# USB.net
KiCad netlist of a schematic drawn in Altium Designer
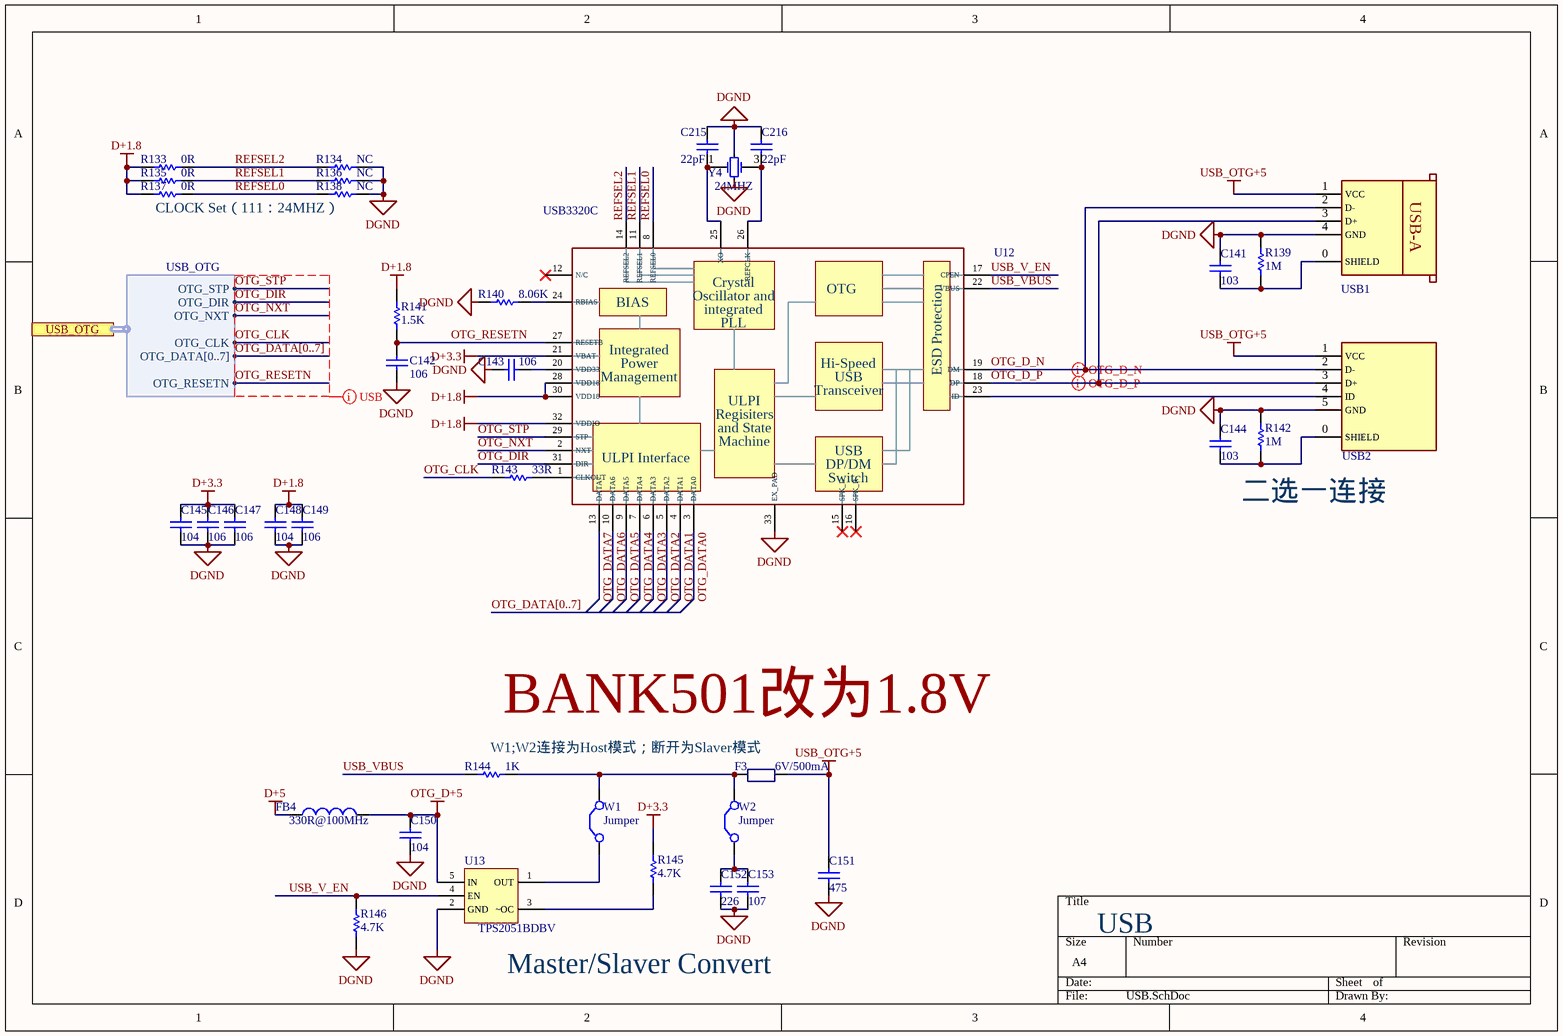
[diagram p0: USB.SchDoc]

(export (version "E")
  (design (tool "Eeschema 10.0.6"))
  (components
    (comp (ref "C141")
      (value "103")
      (footprint "C 0603_L")
      (description "Capacitor")
      (fields (field (name "PUBLISHER") "Altium Limited"))
      (libsource (lib "Miscellaneous Devices") (part "Cap"))
    )
    (comp (ref "C142")
      (value "106")
      (footprint "C 0603_L")
      (description "Capacitor")
      (fields (field (name "PUBLISHER") "Altium Limited"))
      (libsource (lib "Miscellaneous Devices") (part "Cap"))
    )
    (comp (ref "C143")
      (value "106")
      (footprint "C 0603_L")
      (description "Capacitor")
      (fields (field (name "PUBLISHER") "Altium Limited"))
      (libsource (lib "Miscellaneous Devices") (part "Cap"))
    )
    (comp (ref "C144")
      (value "103")
      (footprint "C 0603_L")
      (description "Capacitor")
      (fields (field (name "PUBLISHER") "Altium Limited"))
      (libsource (lib "Miscellaneous Devices") (part "Cap"))
    )
    (comp (ref "C145")
      (value "104")
      (footprint "C 0402_LL")
      (description "Capacitor")
      (fields (field (name "PUBLISHER") "Altium Limited"))
      (libsource (lib "Miscellaneous Devices") (part "Cap"))
    )
    (comp (ref "C146")
      (value "106")
      (footprint "C 0603_L")
      (description "Capacitor")
      (fields (field (name "PUBLISHER") "Altium Limited"))
      (libsource (lib "Miscellaneous Devices") (part "Cap"))
    )
    (comp (ref "C147")
      (value "106")
      (footprint "C 0603_L")
      (description "Capacitor")
      (fields (field (name "PUBLISHER") "Altium Limited"))
      (libsource (lib "Miscellaneous Devices") (part "Cap"))
    )
    (comp (ref "C148")
      (value "104")
      (footprint "C 0402_LL")
      (description "Capacitor")
      (fields (field (name "PUBLISHER") "Altium Limited"))
      (libsource (lib "Miscellaneous Devices") (part "Cap"))
    )
    (comp (ref "C149")
      (value "106")
      (footprint "C 0603_L")
      (description "Capacitor")
      (fields (field (name "PUBLISHER") "Altium Limited"))
      (libsource (lib "Miscellaneous Devices") (part "Cap"))
    )
    (comp (ref "C150")
      (value "104")
      (footprint "C 0402_LL")
      (description "Capacitor")
      (fields (field (name "PUBLISHER") "Altium Limited"))
      (libsource (lib "Miscellaneous Devices") (part "Cap"))
    )
    (comp (ref "C151")
      (value "475")
      (footprint "C 0805_L")
      (description "Capacitor")
      (fields (field (name "PUBLISHER") "Altium Limited"))
      (libsource (lib "Miscellaneous Devices") (part "Cap"))
    )
    (comp (ref "C152")
      (value "226")
      (footprint "C 0805_L")
      (description "Capacitor")
      (fields (field (name "PUBLISHER") "Altium Limited"))
      (libsource (lib "Miscellaneous Devices") (part "Cap"))
    )
    (comp (ref "C153")
      (value "107")
      (footprint "C 1206_L")
      (description "Capacitor")
      (fields (field (name "PUBLISHER") "Altium Limited"))
      (libsource (lib "Miscellaneous Devices") (part "Cap"))
    )
    (comp (ref "C215")
      (value "22pF")
      (footprint "C 0603_L")
      (description "Capacitor")
      (fields (field (name "PUBLISHER") "Altium Limited"))
      (libsource (lib "Miscellaneous Devices") (part "Cap"))
    )
    (comp (ref "C216")
      (value "22pF")
      (footprint "C 0603_L")
      (description "Capacitor")
      (fields (field (name "PUBLISHER") "Altium Limited"))
      (libsource (lib "Miscellaneous Devices") (part "Cap"))
    )
    (comp (ref "F3") (value "6V/500mA") (footprint "FU 0805") (libsource (lib "Sean") (part "PTC")))
    (comp (ref "FB4")
      (value "330R@100MHz")
      (footprint "L 0805")
      (description "Inductor")
      (fields (field (name "Comment") "Ferrite Bead") (field (name "PUBLISHER") "Altium Limited"))
      (libsource (lib "Miscellaneous Devices") (part "Inductor"))
    )
    (comp (ref "R133")
      (value "0R")
      (footprint "R 0402_L")
      (description "Resistor")
      (fields (field (name "PUBLISHER") "Altium Limited"))
      (libsource (lib "Miscellaneous Devices") (part "Res1"))
    )
    (comp (ref "R134")
      (value "NC")
      (footprint "R 0402_L")
      (description "Resistor")
      (fields (field (name "PUBLISHER") "Altium Limited"))
      (libsource (lib "Miscellaneous Devices") (part "Res1"))
    )
    (comp (ref "R135")
      (value "0R")
      (footprint "R 0402_L")
      (description "Resistor")
      (fields (field (name "PUBLISHER") "Altium Limited"))
      (libsource (lib "Miscellaneous Devices") (part "Res1"))
    )
    (comp (ref "R136")
      (value "NC")
      (footprint "R 0402_L")
      (description "Resistor")
      (fields (field (name "PUBLISHER") "Altium Limited"))
      (libsource (lib "Miscellaneous Devices") (part "Res1"))
    )
    (comp (ref "R137")
      (value "0R")
      (footprint "R 0402_L")
      (description "Resistor")
      (fields (field (name "PUBLISHER") "Altium Limited"))
      (libsource (lib "Miscellaneous Devices") (part "Res1"))
    )
    (comp (ref "R138")
      (value "NC")
      (footprint "R 0402_L")
      (description "Resistor")
      (fields (field (name "PUBLISHER") "Altium Limited"))
      (libsource (lib "Miscellaneous Devices") (part "Res1"))
    )
    (comp (ref "R139")
      (value "1M")
      (footprint "R 0603_L")
      (description "Resistor")
      (fields (field (name "PUBLISHER") "Altium Limited"))
      (libsource (lib "Miscellaneous Devices") (part "Res1"))
    )
    (comp (ref "R140")
      (value "8.06K")
      (footprint "R 0603_L")
      (description "Resistor")
      (fields (field (name "PUBLISHER") "Altium Limited"))
      (libsource (lib "Miscellaneous Devices") (part "Res1"))
    )
    (comp (ref "R141")
      (value "1.5K")
      (footprint "R 0603_L")
      (description "Resistor")
      (fields (field (name "PUBLISHER") "Altium Limited"))
      (libsource (lib "Miscellaneous Devices") (part "Res1"))
    )
    (comp (ref "R142")
      (value "1M")
      (footprint "R 0603_L")
      (description "Resistor")
      (fields (field (name "PUBLISHER") "Altium Limited"))
      (libsource (lib "Miscellaneous Devices") (part "Res1"))
    )
    (comp (ref "R143")
      (value "33R")
      (footprint "R 0603_L")
      (description "Resistor")
      (fields (field (name "PUBLISHER") "Altium Limited"))
      (libsource (lib "Miscellaneous Devices") (part "Res1"))
    )
    (comp (ref "R144")
      (value "1K")
      (footprint "R 0603_L")
      (description "Resistor")
      (fields (field (name "PUBLISHER") "Altium Limited"))
      (libsource (lib "Miscellaneous Devices") (part "Res1"))
    )
    (comp (ref "R145")
      (value "4.7K")
      (footprint "R 0603_L")
      (description "Resistor")
      (fields (field (name "PUBLISHER") "Altium Limited"))
      (libsource (lib "Miscellaneous Devices") (part "Res1"))
    )
    (comp (ref "R146")
      (value "4.7K")
      (footprint "R 0603_L")
      (description "Resistor")
      (fields (field (name "PUBLISHER") "Altium Limited"))
      (libsource (lib "Miscellaneous Devices") (part "Res1"))
    )
    (comp (ref "U12")
      (value "USB3320C")
      (footprint "QFN32 5x5_M")
      (description "USB PHY")
      (libsource (lib "ZYNQ7010_add") (part "USB3320C_re"))
    )
    (comp (ref "U13")
      (value "TPS2051BDBV")
      (footprint "SOT23-5N")
      (description "Current-Limited, Power-Distribution Switches")
      (libsource (lib "ZYNQ7010_add") (part "TPS2051BDBV"))
    )
    (comp (ref "USB1")
      (value "USB_A,B/S")
      (footprint "USB-A/S_A")
      (libsource (lib "Schlib1") (part "USB_A,B/S"))
    )
    (comp (ref "USB2")
      (value "USB_miniB,microB")
      (footprint "USB-MINI-A")
      (libsource (lib "Schlib1") (part "USB_miniB,microB"))
    )
    (comp (ref "W1")
      (value "Jumper")
      (footprint "HDR2.54-LI-2P")
      (description "Jumper Wire")
      (fields (field (name "PUBLISHER") "Altium Limited"))
      (libsource (lib "Miscellaneous Devices") (part "Jumper"))
    )
    (comp (ref "W2")
      (value "Jumper")
      (footprint "HDR2.54-LI-2P")
      (description "Jumper Wire")
      (fields (field (name "PUBLISHER") "Altium Limited"))
      (libsource (lib "Miscellaneous Devices") (part "Jumper"))
    )
    (comp (ref "Y4")
      (value "24MHZ")
      (footprint "OSC 5032-4P")
      (description "无源晶振")
      (fields (field (name "MANUFACTURER") "NC"))
      (libsource (lib "ZYNQ7010_add") (part "XTAL-4-N"))
    )
  )
  (nets
    (net (code "2") (name "/OTG_CLK") (class "Default")
      (node (ref "R143") (pin "1") (pinfunction "1_1") (pintype "passive"))
    )
    (net (code "3") (name "/OTG_DATA0") (class "Default")
      (node (ref "U12") (pin "3") (pinfunction "DATA0_3") (pintype "passive"))
    )
    (net (code "4") (name "/OTG_DATA1") (class "Default")
      (node (ref "U12") (pin "4") (pinfunction "DATA1_4") (pintype "passive"))
    )
    (net (code "5") (name "/OTG_DATA2") (class "Default")
      (node (ref "U12") (pin "5") (pinfunction "DATA2_5") (pintype "passive"))
    )
    (net (code "6") (name "/OTG_DATA3") (class "Default")
      (node (ref "U12") (pin "6") (pinfunction "DATA3_6") (pintype "passive"))
    )
    (net (code "7") (name "/OTG_DATA4") (class "Default")
      (node (ref "U12") (pin "7") (pinfunction "DATA4_7") (pintype "passive"))
    )
    (net (code "8") (name "/OTG_DATA5") (class "Default")
      (node (ref "U12") (pin "9") (pinfunction "DATA5_9") (pintype "passive"))
    )
    (net (code "9") (name "/OTG_DATA6") (class "Default")
      (node (ref "U12") (pin "10") (pinfunction "DATA6_10") (pintype "passive"))
    )
    (net (code "10") (name "/OTG_DATA7") (class "Default")
      (node (ref "U12") (pin "13") (pinfunction "DATA7_13") (pintype "passive"))
    )
    (net (code "12") (name "/OTG_DIR") (class "Default")
      (node (ref "U12") (pin "31") (pinfunction "DIR_31") (pintype "passive"))
    )
    (net (code "13") (name "/OTG_D_N") (class "Default")
      (node (ref "U12") (pin "19") (pinfunction "DM_19") (pintype "passive"))
      (node (ref "USB1") (pin "2") (pinfunction "D-_2") (pintype "passive"))
      (node (ref "USB2") (pin "2") (pinfunction "D-_2") (pintype "passive"))
    )
    (net (code "14") (name "/OTG_D_P") (class "Default")
      (node (ref "U12") (pin "18") (pinfunction "DP_18") (pintype "passive"))
      (node (ref "USB1") (pin "3") (pinfunction "D+_3") (pintype "passive"))
      (node (ref "USB2") (pin "3") (pinfunction "D+_3") (pintype "passive"))
    )
    (net (code "15") (name "/OTG_NXT") (class "Default")
      (node (ref "U12") (pin "2") (pinfunction "NXT_2") (pintype "passive"))
    )
    (net (code "16") (name "/OTG_RESETN") (class "Default")
      (node (ref "C142") (pin "1") (pinfunction "1_1") (pintype "passive"))
      (node (ref "R141") (pin "1") (pinfunction "1_1") (pintype "passive"))
      (node (ref "U12") (pin "27") (pinfunction "RESETB_27") (pintype "passive"))
    )
    (net (code "17") (name "/OTG_STP") (class "Default")
      (node (ref "U12") (pin "29") (pinfunction "STP_29") (pintype "passive"))
    )
    (net (code "18") (name "/REFSEL0") (class "Default")
      (node (ref "R137") (pin "1") (pinfunction "1_1") (pintype "passive"))
      (node (ref "R138") (pin "2") (pinfunction "2_2") (pintype "passive"))
      (node (ref "U12") (pin "8") (pinfunction "REFSEL0_8") (pintype "passive"))
    )
    (net (code "19") (name "/REFSEL1") (class "Default")
      (node (ref "R135") (pin "1") (pinfunction "1_1") (pintype "passive"))
      (node (ref "R136") (pin "2") (pinfunction "2_2") (pintype "passive"))
      (node (ref "U12") (pin "11") (pinfunction "REFSEL1_11") (pintype "passive"))
    )
    (net (code "20") (name "/REFSEL2") (class "Default")
      (node (ref "R133") (pin "1") (pinfunction "1_1") (pintype "passive"))
      (node (ref "R134") (pin "2") (pinfunction "2_2") (pintype "passive"))
      (node (ref "U12") (pin "14") (pinfunction "REFSEL2_14") (pintype "passive"))
    )
    (net (code "22") (name "/USB_VBUS") (class "Default")
      (node (ref "R144") (pin "2") (pinfunction "2_2") (pintype "passive"))
      (node (ref "U12") (pin "22") (pinfunction "VBUS_22") (pintype "passive"))
    )
    (net (code "23") (name "/USB_V_EN") (class "Default")
      (node (ref "R146") (pin "2") (pinfunction "2_2") (pintype "passive"))
      (node (ref "U12") (pin "17") (pinfunction "CPEN_17") (pintype "passive"))
      (node (ref "U13") (pin "4") (pinfunction "EN_4") (pintype "passive"))
    )
    (net (code "25") (name "D+1.8") (class "Default")
      (node (ref "C148") (pin "1") (pinfunction "1_1") (pintype "passive"))
      (node (ref "C149") (pin "1") (pinfunction "1_1") (pintype "passive"))
      (node (ref "R133") (pin "2") (pinfunction "2_2") (pintype "passive"))
      (node (ref "R135") (pin "2") (pinfunction "2_2") (pintype "passive"))
      (node (ref "R137") (pin "2") (pinfunction "2_2") (pintype "passive"))
      (node (ref "R141") (pin "2") (pinfunction "2_2") (pintype "passive"))
      (node (ref "U12") (pin "28") (pinfunction "VDD18_28") (pintype "passive"))
      (node (ref "U12") (pin "30") (pinfunction "VDD18_30") (pintype "passive"))
      (node (ref "U12") (pin "32") (pinfunction "VDDIO_32") (pintype "passive"))
    )
    (net (code "26") (name "D+3.3") (class "Default")
      (node (ref "C145") (pin "1") (pinfunction "1_1") (pintype "passive"))
      (node (ref "C146") (pin "1") (pinfunction "1_1") (pintype "passive"))
      (node (ref "C147") (pin "1") (pinfunction "1_1") (pintype "passive"))
      (node (ref "R145") (pin "2") (pinfunction "2_2") (pintype "passive"))
      (node (ref "U12") (pin "21") (pinfunction "VBAT_21") (pintype "passive"))
    )
    (net (code "27") (name "D+5") (class "Default")
      (node (ref "FB4") (pin "1") (pinfunction "1_1") (pintype "passive"))
    )
    (net (code "28") (name "DGND") (class "Default")
      (node (ref "C141") (pin "1") (pinfunction "1_1") (pintype "passive"))
      (node (ref "C142") (pin "2") (pinfunction "2_2") (pintype "passive"))
      (node (ref "C143") (pin "2") (pinfunction "2_2") (pintype "passive"))
      (node (ref "C144") (pin "1") (pinfunction "1_1") (pintype "passive"))
      (node (ref "C145") (pin "2") (pinfunction "2_2") (pintype "passive"))
      (node (ref "C146") (pin "2") (pinfunction "2_2") (pintype "passive"))
      (node (ref "C147") (pin "2") (pinfunction "2_2") (pintype "passive"))
      (node (ref "C148") (pin "2") (pinfunction "2_2") (pintype "passive"))
      (node (ref "C149") (pin "2") (pinfunction "2_2") (pintype "passive"))
      (node (ref "C150") (pin "2") (pinfunction "2_2") (pintype "passive"))
      (node (ref "C151") (pin "2") (pinfunction "2_2") (pintype "passive"))
      (node (ref "C152") (pin "2") (pinfunction "2_2") (pintype "passive"))
      (node (ref "C153") (pin "2") (pinfunction "2_2") (pintype "passive"))
      (node (ref "C215") (pin "1") (pinfunction "1_1") (pintype "passive"))
      (node (ref "C216") (pin "1") (pinfunction "1_1") (pintype "passive"))
      (node (ref "R134") (pin "1") (pinfunction "1_1") (pintype "passive"))
      (node (ref "R136") (pin "1") (pinfunction "1_1") (pintype "passive"))
      (node (ref "R138") (pin "1") (pinfunction "1_1") (pintype "passive"))
      (node (ref "R139") (pin "2") (pinfunction "2_2") (pintype "passive"))
      (node (ref "R140") (pin "1") (pinfunction "1_1") (pintype "passive"))
      (node (ref "R142") (pin "2") (pinfunction "2_2") (pintype "passive"))
      (node (ref "R146") (pin "1") (pinfunction "1_1") (pintype "passive"))
      (node (ref "U12") (pin "33") (pinfunction "EX_PAD_33") (pintype "passive"))
      (node (ref "U13") (pin "2") (pinfunction "GND_2") (pintype "passive"))
      (node (ref "USB1") (pin "4") (pinfunction "GND_4") (pintype "passive"))
      (node (ref "USB2") (pin "5") (pinfunction "GND_5") (pintype "passive"))
      (node (ref "Y4") (pin "2") (pinfunction "2_2") (pintype "passive"))
      (node (ref "Y4") (pin "4") (pinfunction "4_4") (pintype "passive"))
    )
    (net (code "29") (name "Net-(U12-CLKOUT)") (class "Default")
      (node (ref "R143") (pin "2") (pinfunction "2_2") (pintype "passive"))
      (node (ref "U12") (pin "1") (pinfunction "CLKOUT_1") (pintype "passive"))
    )
    (net (code "30") (name "Net-(U12-ID)") (class "Default")
      (node (ref "U12") (pin "23") (pinfunction "ID_23") (pintype "passive"))
      (node (ref "USB2") (pin "4") (pinfunction "ID_4") (pintype "passive"))
    )
    (net (code "31") (name "Net-(U12-RBIAS)") (class "Default")
      (node (ref "R140") (pin "2") (pinfunction "2_2") (pintype "passive"))
      (node (ref "U12") (pin "24") (pinfunction "RBIAS_24") (pintype "passive"))
    )
    (net (code "32") (name "Net-(U12-REFCLK)") (class "Default")
      (node (ref "C216") (pin "2") (pinfunction "2_2") (pintype "passive"))
      (node (ref "U12") (pin "26") (pinfunction "REFCLK_26") (pintype "passive"))
      (node (ref "Y4") (pin "3") (pinfunction "OSC2_3") (pintype "passive"))
    )
    (net (code "33") (name "Net-(U12-VDD33)") (class "Default")
      (node (ref "C143") (pin "1") (pinfunction "1_1") (pintype "passive"))
      (node (ref "U12") (pin "20") (pinfunction "VDD33_20") (pintype "passive"))
    )
    (net (code "34") (name "Net-(U12-XO)") (class "Default")
      (node (ref "C215") (pin "2") (pinfunction "2_2") (pintype "passive"))
      (node (ref "U12") (pin "25") (pinfunction "XO_25") (pintype "passive"))
      (node (ref "Y4") (pin "1") (pinfunction "OSC1_1") (pintype "passive"))
    )
    (net (code "35") (name "Net-(U13-OUT)") (class "Default")
      (node (ref "U13") (pin "1") (pinfunction "OUT_1") (pintype "passive"))
      (node (ref "W1") (pin "1") (pinfunction "C1_1") (pintype "passive"))
    )
    (net (code "36") (name "Net-(U13-~OC)") (class "Default")
      (node (ref "R145") (pin "1") (pinfunction "1_1") (pintype "passive"))
      (node (ref "U13") (pin "3") (pinfunction "~OC_3") (pintype "passive"))
    )
    (net (code "37") (name "Net-(USB1-SHIELD)") (class "Default")
      (node (ref "C141") (pin "2") (pinfunction "2_2") (pintype "passive"))
      (node (ref "R139") (pin "1") (pinfunction "1_1") (pintype "passive"))
      (node (ref "USB1") (pin "0") (pinfunction "SHIELD_0") (pintype "passive"))
    )
    (net (code "38") (name "Net-(USB2-SHIELD)") (class "Default")
      (node (ref "C144") (pin "2") (pinfunction "2_2") (pintype "passive"))
      (node (ref "R142") (pin "1") (pinfunction "1_1") (pintype "passive"))
      (node (ref "USB2") (pin "0") (pinfunction "SHIELD_0") (pintype "passive"))
    )
    (net (code "39") (name "Net-(W1-C2)") (class "Default")
      (node (ref "F3") (pin "2") (pinfunction "2_2") (pintype "passive"))
      (node (ref "R144") (pin "1") (pinfunction "1_1") (pintype "passive"))
      (node (ref "W1") (pin "2") (pinfunction "C2_2") (pintype "passive"))
      (node (ref "W2") (pin "2") (pinfunction "C2_2") (pintype "passive"))
    )
    (net (code "40") (name "Net-(W2-C1)") (class "Default")
      (node (ref "C152") (pin "1") (pinfunction "1_1") (pintype "passive"))
      (node (ref "C153") (pin "1") (pinfunction "1_1") (pintype "passive"))
      (node (ref "W2") (pin "1") (pinfunction "C1_1") (pintype "passive"))
    )
    (net (code "41") (name "OTG_D+5") (class "Default")
      (node (ref "C150") (pin "1") (pinfunction "1_1") (pintype "passive"))
      (node (ref "FB4") (pin "2") (pinfunction "2_2") (pintype "passive"))
      (node (ref "U13") (pin "5") (pinfunction "IN_5") (pintype "passive"))
    )
    (net (code "42") (name "USB_OTG+5") (class "Default")
      (node (ref "C151") (pin "1") (pinfunction "1_1") (pintype "passive"))
      (node (ref "F3") (pin "1") (pinfunction "1_1") (pintype "passive"))
      (node (ref "USB1") (pin "1") (pinfunction "VCC_1") (pintype "passive"))
      (node (ref "USB2") (pin "1") (pinfunction "VCC_1") (pintype "passive"))
    )
    (net (code "43") (name "unconnected-(U12-N{slash}C-Pad12)") (class "Default")
      (node (ref "U12") (pin "12") (pinfunction "N/C_12") (pintype "passive+no_connect"))
    )
    (net (code "44") (name "unconnected-(U12-SPK_L-Pad15)") (class "Default")
      (node (ref "U12") (pin "15") (pinfunction "SPK_L_15") (pintype "passive+no_connect"))
    )
    (net (code "45") (name "unconnected-(U12-SPK_R-Pad16)") (class "Default")
      (node (ref "U12") (pin "16") (pinfunction "SPK_R_16") (pintype "passive+no_connect"))
    )
  )
)
